# Power.net
KiCad netlist of a schematic drawn in Altium Designer
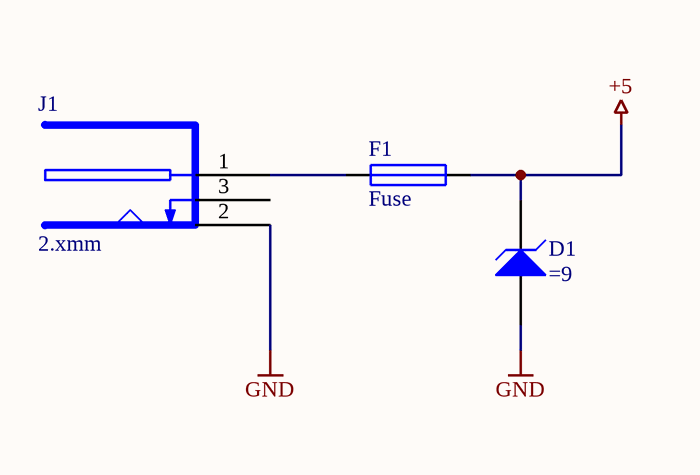
[diagram p0: Power.SchDoc]

(export (version "E")
  (design (tool "Eeschema 10.0.6"))
  (components
    (comp (ref "D1")
      (value "~")
      (footprint "FP_SMA")
      (description "Zener Diode")
      (libsource (lib "hallglib") (part "ZENER"))
    )
    (comp (ref "F1") (value "Fuse") (footprint "FP_MULTIFUSE") (libsource (lib "hallglib") (part "Fuse")))
    (comp (ref "J1")
      (value "2.xmm")
      (footprint "FP_DC_TAP_ANYA")
      (description "2.xmm DC HEBA25 TÁPFESZÜLTSÉG ALJZAT ZÁRT, NYÁKBA 90°")
      (libsource (lib "hallglib") (part "DC_TAP_ANYA"))
    )
  )
  (nets
    (net (code "1") (name "+5") (class "Default")
      (node (ref "D1") (pin "2") (pinfunction "K_2") (pintype "passive"))
      (node (ref "F1") (pin "2") (pinfunction "2_2") (pintype "passive"))
    )
    (net (code "2") (name "GND") (class "Default")
      (node (ref "D1") (pin "1") (pinfunction "A_1") (pintype "passive"))
      (node (ref "J1") (pin "2") (pinfunction "SLEEVE_2") (pintype "power_in"))
    )
    (net (code "3") (name "Net-(J1-PIN)") (class "Default")
      (node (ref "F1") (pin "1") (pinfunction "1_1") (pintype "passive"))
      (node (ref "J1") (pin "1") (pinfunction "PIN_1") (pintype "power_in"))
    )
    (net (code "4") (name "unconnected-(J1-BREAK-Pad3)") (class "Default")
      (node (ref "J1") (pin "3") (pinfunction "BREAK_3") (pintype "power_in"))
    )
  )
)
